# Supply.net
KiCad netlist of a schematic drawn in Altium Designer
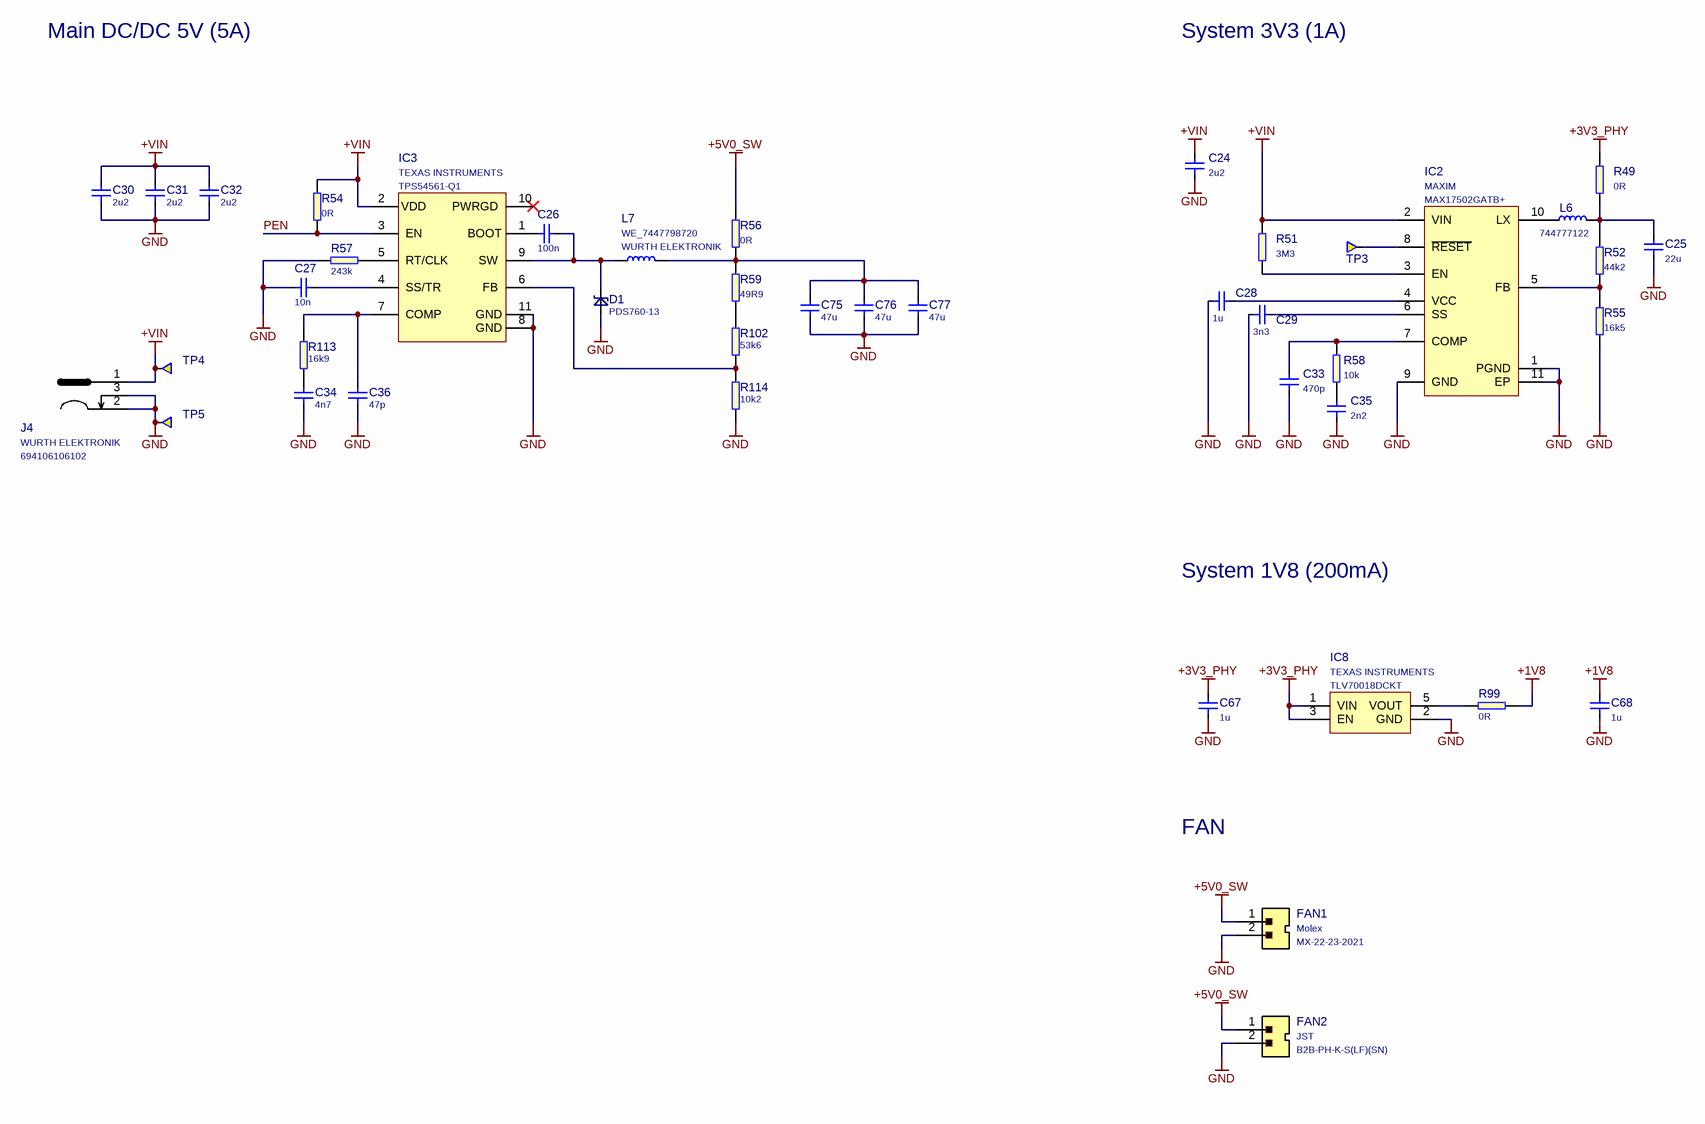
[diagram p0: Supply.SchDoc]

(export (version "E")
  (design (tool "Eeschema 10.0.6"))
  (components
    (comp (ref "C24")
      (value "2u2")
      (footprint "1210")
      (description "MLCC SMT Capacitor 2u2F 1210")
      (fields (field (name "PARTNUMBER") "C_2u2_1210"))
      (libsource (lib "altium-import") (part "root_1_C_"))
    )
    (comp (ref "C25")
      (value "22u")
      (footprint "1210")
      (description "MLCC SMT Capacitor 22uF 1210")
      (fields (field (name "PARTNUMBER") "C_22u_1210"))
      (libsource (lib "altium-import") (part "root_1_C_"))
    )
    (comp (ref "C26")
      (value "100n")
      (footprint "0603")
      (description "MLCC SMT Capacitor 100nF 0603")
      (fields (field (name "PARTNUMBER") "C_100n_0603") (field (name "MANUFACTURER") "AVX"))
      (libsource (lib "altium-import") (part "root_0_C_"))
    )
    (comp (ref "C27")
      (value "10n")
      (footprint "0402")
      (description "MLCC SMT Capacitor 10nF 0402")
      (fields (field (name "PARTNUMBER") "C_10n_0402") (field (name "MANUFACTURER") "AVX"))
      (libsource (lib "altium-import") (part "root_0_C_"))
    )
    (comp (ref "C28")
      (value "1u")
      (footprint "C_0402")
      (description "MLCC SMT Capacitor 1uF 0402")
      (fields (field (name "PARTNUMBER") "C_1u_0402"))
      (libsource (lib "altium-import") (part "root_0_C_"))
    )
    (comp (ref "C29")
      (value "3n3")
      (footprint "0603")
      (description "MLCC SMT Capacitor 3n3F 0603")
      (fields (field (name "PARTNUMBER") "C_3n3_0603"))
      (libsource (lib "altium-import") (part "root_0_C_"))
    )
    (comp (ref "C30")
      (value "2u2")
      (footprint "1206")
      (description "MLCC SMT Capacitor 2u2F 1206")
      (fields (field (name "PARTNUMBER") "C_2u2_1206") (field (name "MANUFACTURER") "Kemet"))
      (libsource (lib "altium-import") (part "root_1_C_"))
    )
    (comp (ref "C31")
      (value "2u2")
      (footprint "1206")
      (description "MLCC SMT Capacitor 2u2F 1206")
      (fields (field (name "PARTNUMBER") "C_2u2_1206") (field (name "MANUFACTURER") "Kemet"))
      (libsource (lib "altium-import") (part "root_1_C_"))
    )
    (comp (ref "C32")
      (value "2u2")
      (footprint "1206")
      (description "MLCC SMT Capacitor 2u2F 1206")
      (fields (field (name "PARTNUMBER") "C_2u2_1206") (field (name "MANUFACTURER") "Kemet"))
      (libsource (lib "altium-import") (part "root_1_C_"))
    )
    (comp (ref "C33")
      (value "470p")
      (footprint "0603")
      (description "MLCC SMT Capacitor 470pF 0603")
      (fields (field (name "PARTNUMBER") "C_470p_0603"))
      (libsource (lib "altium-import") (part "root_1_C_"))
    )
    (comp (ref "C34")
      (value "4n7")
      (footprint "0402")
      (description "MLCC SMT Capacitor 4n7F 0402")
      (fields (field (name "PARTNUMBER") "C_4n7_0402") (field (name "MANUFACTURER") "TDK"))
      (libsource (lib "altium-import") (part "root_1_C_"))
    )
    (comp (ref "C35")
      (value "2n2")
      (footprint "0603")
      (description "MLCC SMT Capacitor 2n2F 0603")
      (fields (field (name "PARTNUMBER") "C_2n2_0603"))
      (libsource (lib "altium-import") (part "root_1_C_"))
    )
    (comp (ref "C36")
      (value "47p")
      (footprint "0402")
      (description "MLCC SMT Capacitor 47pF 0402")
      (fields (field (name "PARTNUMBER") "C_47p_0402") (field (name "MANUFACTURER") "KEMET"))
      (libsource (lib "altium-import") (part "root_1_C_"))
    )
    (comp (ref "C67")
      (value "1u")
      (footprint "C_0402")
      (description "MLCC SMT Capacitor 1uF 0402")
      (fields (field (name "PARTNUMBER") "C_1u_0402"))
      (libsource (lib "altium-import") (part "root_1_C_"))
    )
    (comp (ref "C68")
      (value "1u")
      (footprint "C_0402")
      (description "MLCC SMT Capacitor 1uF 0402")
      (fields (field (name "PARTNUMBER") "C_1u_0402"))
      (libsource (lib "altium-import") (part "root_1_C_"))
    )
    (comp (ref "C75")
      (value "47u")
      (footprint "0805")
      (description "MLCC SMT Capacitor 47uF 0805")
      (fields (field (name "PARTNUMBER") "C_47u_0805") (field (name "MANUFACTURER") "KEMET"))
      (libsource (lib "altium-import") (part "root_1_C_"))
    )
    (comp (ref "C76")
      (value "47u")
      (footprint "0805")
      (description "MLCC SMT Capacitor 47uF 0805")
      (fields (field (name "PARTNUMBER") "C_47u_0805") (field (name "MANUFACTURER") "KEMET"))
      (libsource (lib "altium-import") (part "root_1_C_"))
    )
    (comp (ref "C77")
      (value "47u")
      (footprint "0805")
      (description "MLCC SMT Capacitor 47uF 0805")
      (fields (field (name "PARTNUMBER") "C_47u_0805") (field (name "MANUFACTURER") "KEMET"))
      (libsource (lib "altium-import") (part "root_1_C_"))
    )
    (comp (ref "D1")
      (value "PDS760-13")
      (footprint "PowerDI")
      (description "Schottky Diodes & Rectifiers SCHOTTKY RECTIFIER")
      (fields (field (name "MANUFACTURER") "DIODES INC."))
      (libsource (lib "altium-import") (part "root_0_Diode Schottky_"))
    )
    (comp (ref "FAN1")
      (value "MX-22-23-2021")
      (footprint "molex_2223-2021")
      (description "Pinhead connector with key")
      (fields (field (name "MANUFACTURER") "Molex") (field (name "PARTNUMBER") "022232021 A-6373-02A222"))
      (libsource (lib "altium-import") (part "root_0_molex_2223-2021_"))
    )
    (comp (ref "FAN2")
      (value "B2B-PH-K-S(LF)(SN)")
      (footprint "B2B-PH-K-S(LF)(SN)")
      (fields (field (name "MANUFACTURER") "JST"))
      (libsource (lib "coral-baseboard") (part "B2B-PH-K-S(LF)(SN)"))
    )
    (comp (ref "IC2")
      (value "MAX17502GATB+")
      (footprint "10-TDFN")
      (fields (field (name "MANUFACTURER") "MAXIM"))
      (libsource (lib "altium-import") (part "root_0_MAX17502G_"))
    )
    (comp (ref "IC3")
      (value "TPS54561-Q1")
      (footprint "WSON-10_4x4")
      (description "IC REG BCK SPLIT RAIL ADJ 10WSON")
      (fields (field (name "MANUFACTURER") "TEXAS INSTRUMENTS"))
      (libsource (lib "altium-import") (part "root_0_TPS54561_"))
    )
    (comp (ref "IC8")
      (value "TLV70018DCKT")
      (footprint "SC70-5")
      (description "Voltage Regulator, 2V to 5.5V, 175mV Dropout, 1.8Vout, 200mAout")
      (fields (field (name "MANUFACTURER") "TEXAS INSTRUMENTS"))
      (libsource (lib "altium-import") (part "root_0_TLV700_"))
    )
    (comp (ref "J4")
      (value "694106106102")
      (footprint "694106106102")
      (description "DC Power Jack Right Angled SMT Ø6.4 with 4 soldering pads & pegs WR-DC")
      (fields (field (name "MANUFACTURER") "WURTH ELEKTRONIK") (field (name "PARTNUMBER") "694106106102"))
      (libsource (lib "altium-import") (part "root_0_DC_SOCKET_2_"))
    )
    (comp (ref "L6")
      (value "744777122")
      (footprint "WE_744777122")
      (description "Surface Mount Power Inductor, WE-PD Series, 22 µH, 1.41 A, 1.7 A, Shielded, 0.11 ohm")
      (fields (field (name "MANUFACTURER") "WURTH ELEKTRONIK"))
      (libsource (lib "altium-import") (part "root_0_Inductor SMT_"))
    )
    (comp (ref "L7")
      (value "WE_7447798720")
      (footprint "WE_7447798720")
      (description "Fixed Inductors WE-PDF 1064 7.2uH 7.9A 12.8mOhm")
      (fields (field (name "PARTNUMBER") "WE_7447798720") (field (name "MANUFACTURER") "WURTH ELEKTRONIK"))
      (libsource (lib "altium-import") (part "root_0_Inductor SMT_"))
    )
    (comp (ref "R49")
      (value "0R")
      (footprint "0805")
      (description "SMT Resistor 0R 0805")
      (fields (field (name "PARTNUMBER") "R_0R_0805"))
      (libsource (lib "altium-import") (part "root_1_R_"))
    )
    (comp (ref "R51")
      (value "3M3")
      (footprint "0402")
      (description "SMT Resistor 3M3 0402")
      (fields (field (name "PARTNUMBER") "R_3M3_0402"))
      (libsource (lib "altium-import") (part "root_1_R_"))
    )
    (comp (ref "R52")
      (value "44k2")
      (footprint "0402")
      (description "SMT Resistor 0402")
      (fields (field (name "PARTNUMBER") "R_44k2_0402"))
      (libsource (lib "altium-import") (part "root_1_R_"))
    )
    (comp (ref "R54")
      (value "0R")
      (footprint "0402")
      (description "SMT Resistor 0402")
      (fields (field (name "PARTNUMBER") "R_0R_0402"))
      (libsource (lib "altium-import") (part "root_1_R_0R_0402_"))
    )
    (comp (ref "R55")
      (value "16k5")
      (footprint "0402")
      (description "RES, 16k5, 0402, 0.1%")
      (fields (field (name "PARTNUMBER") "R_16k5_0402_0.1%"))
      (libsource (lib "altium-import") (part "root_1_R_"))
    )
    (comp (ref "R56")
      (value "0R")
      (footprint "1206")
      (description "RES, 0R, 1206")
      (fields (field (name "PARTNUMBER") "R_0R_1206"))
      (libsource (lib "altium-import") (part "root_1_R_0R_1206_"))
    )
    (comp (ref "R57")
      (value "243k")
      (footprint "0402")
      (description "RES, 243k, 0402")
      (fields (field (name "PARTNUMBER") "R_243k_0402"))
      (libsource (lib "altium-import") (part "root_2_R_243k_0402_"))
    )
    (comp (ref "R58")
      (value "10k")
      (footprint "0402")
      (description "SMT Resistor 0402")
      (fields (field (name "PARTNUMBER") "R_10k_0402"))
      (libsource (lib "altium-import") (part "root_1_R_"))
    )
    (comp (ref "R59")
      (value "49R9")
      (footprint "0402")
      (description "RES, 49R9, 0402")
      (fields (field (name "PARTNUMBER") "R_49R9_0402"))
      (libsource (lib "altium-import") (part "root_1_R_49R9_0402_"))
    )
    (comp (ref "R99")
      (value "0R")
      (footprint "0603")
      (description "SMT Resistor 0R 0603")
      (fields (field (name "PARTNUMBER") "R_0R_0603"))
      (libsource (lib "altium-import") (part "root_0_R_"))
    )
    (comp (ref "R102")
      (value "53k6")
      (footprint "0402")
      (description "SMT Resistor 0402")
      (fields (field (name "PARTNUMBER") "R_53k6_0402") (field (name "MANUFACTURER") "TE CONNECTIVITY"))
      (libsource (lib "altium-import") (part "root_1_R_"))
    )
    (comp (ref "R113")
      (value "16k9")
      (footprint "0402")
      (description "SMT Resistor 0402")
      (fields (field (name "PARTNUMBER") "R_16k9_0402") (field (name "MANUFACTURER") "PANASONIC"))
      (libsource (lib "altium-import") (part "root_1_R_"))
    )
    (comp (ref "R114")
      (value "10k2")
      (footprint "0402")
      (description "RES, 10k2, 0402, 0.1%")
      (fields (field (name "PARTNUMBER") "R_10k2_0402_0.1%") (field (name "MANUFACTURER") "TE CONECTIVITY"))
      (libsource (lib "altium-import") (part "root_1_R_"))
    )
    (comp (ref "TP3")
      (value "~")
      (footprint "TP-R-2.5")
      (description "Testpad, round, 2mm")
      (fields (field (name "PARTNUMBER") "Testpad"))
      (libsource (lib "altium-import") (part "root_1_Testpad_"))
    )
    (comp (ref "TP4")
      (value "Testpad")
      (footprint "TP-R-1.5")
      (description "Testpad, round, 1.5mm")
      (libsource (lib "altium-import") (part "root_3_Testpad_"))
    )
    (comp (ref "TP5")
      (value "Testpad")
      (footprint "TP-R-1.5")
      (description "Testpad, round, 1.5mm")
      (libsource (lib "altium-import") (part "root_3_Testpad_"))
    )
  )
  (nets
    (net (code "1") (name "+1V8") (class "Default")
      (node (ref "C68") (pin "2") (pinfunction "2_2") (pintype "passive"))
      (node (ref "R99") (pin "2") (pintype "passive"))
    )
    (net (code "2") (name "+3V3_PHY") (class "Default")
      (node (ref "C67") (pin "2") (pinfunction "2_2") (pintype "passive"))
      (node (ref "IC8") (pin "1") (pinfunction "VIN_1") (pintype "passive"))
      (node (ref "IC8") (pin "3") (pinfunction "EN_3") (pintype "passive"))
      (node (ref "R49") (pin "2") (pintype "passive"))
    )
    (net (code "3") (name "+5V0_SW") (class "Default")
      (node (ref "FAN1") (pin "1") (pinfunction "1_1") (pintype "passive"))
      (node (ref "FAN2") (pin "1") (pinfunction "1_1") (pintype "passive"))
      (node (ref "R56") (pin "2") (pintype "passive"))
    )
    (net (code "4") (name "+VIN") (class "Default")
      (node (ref "C24") (pin "2") (pinfunction "2_2") (pintype "passive"))
      (node (ref "C30") (pin "2") (pinfunction "2_2") (pintype "passive"))
      (node (ref "C31") (pin "2") (pinfunction "2_2") (pintype "passive"))
      (node (ref "C32") (pin "2") (pinfunction "2_2") (pintype "passive"))
      (node (ref "IC2") (pin "2") (pinfunction "VIN_2") (pintype "passive"))
      (node (ref "IC3") (pin "2") (pinfunction "VDD_2") (pintype "passive"))
      (node (ref "J4") (pin "1") (pinfunction "1_1") (pintype "passive"))
      (node (ref "R51") (pin "2") (pintype "passive"))
      (node (ref "R54") (pin "2") (pintype "passive"))
      (node (ref "TP4") (pin "1") (pintype "passive"))
    )
    (net (code "5") (name "/PEN") (class "Default")
      (node (ref "IC3") (pin "3") (pinfunction "EN_3") (pintype "passive"))
      (node (ref "R54") (pin "1") (pintype "passive"))
    )
    (net (code "6") (name "GND") (class "Default")
      (node (ref "C24") (pin "1") (pinfunction "1_1") (pintype "passive"))
      (node (ref "C25") (pin "1") (pinfunction "1_1") (pintype "passive"))
      (node (ref "C27") (pin "1") (pinfunction "1_1") (pintype "passive"))
      (node (ref "C28") (pin "1") (pinfunction "1_1") (pintype "passive"))
      (node (ref "C29") (pin "1") (pinfunction "1_1") (pintype "passive"))
      (node (ref "C30") (pin "1") (pinfunction "1_1") (pintype "passive"))
      (node (ref "C31") (pin "1") (pinfunction "1_1") (pintype "passive"))
      (node (ref "C32") (pin "1") (pinfunction "1_1") (pintype "passive"))
      (node (ref "C33") (pin "1") (pinfunction "1_1") (pintype "passive"))
      (node (ref "C34") (pin "1") (pinfunction "1_1") (pintype "passive"))
      (node (ref "C35") (pin "1") (pinfunction "1_1") (pintype "passive"))
      (node (ref "C36") (pin "1") (pinfunction "1_1") (pintype "passive"))
      (node (ref "C67") (pin "1") (pinfunction "1_1") (pintype "passive"))
      (node (ref "C68") (pin "1") (pinfunction "1_1") (pintype "passive"))
      (node (ref "C75") (pin "1") (pinfunction "1_1") (pintype "passive"))
      (node (ref "C76") (pin "1") (pinfunction "1_1") (pintype "passive"))
      (node (ref "C77") (pin "1") (pinfunction "1_1") (pintype "passive"))
      (node (ref "D1") (pin "A") (pinfunction "A_A") (pintype "passive"))
      (node (ref "FAN1") (pin "2") (pinfunction "2_2") (pintype "passive"))
      (node (ref "FAN2") (pin "2") (pinfunction "2_2") (pintype "passive"))
      (node (ref "IC2") (pin "1") (pinfunction "PGND_1") (pintype "passive"))
      (node (ref "IC2") (pin "11") (pinfunction "EP_11") (pintype "passive"))
      (node (ref "IC2") (pin "9") (pinfunction "GND_9") (pintype "passive"))
      (node (ref "IC3") (pin "11") (pinfunction "GND_11") (pintype "passive"))
      (node (ref "IC3") (pin "8") (pinfunction "GND_8") (pintype "passive"))
      (node (ref "IC8") (pin "2") (pinfunction "GND_2") (pintype "passive"))
      (node (ref "J4") (pin "2") (pinfunction "2_2") (pintype "passive"))
      (node (ref "J4") (pin "3") (pinfunction "3_3") (pintype "passive"))
      (node (ref "R114") (pin "1") (pintype "passive"))
      (node (ref "R55") (pin "1") (pintype "passive"))
      (node (ref "R57") (pin "2") (pintype "passive"))
      (node (ref "TP5") (pin "1") (pintype "passive"))
    )
    (net (code "7") (name "Net-(C25-Pad2)") (class "Default")
      (node (ref "C25") (pin "2") (pinfunction "2_2") (pintype "passive"))
      (node (ref "L6") (pin "2") (pintype "passive"))
      (node (ref "R49") (pin "1") (pintype "passive"))
      (node (ref "R52") (pin "2") (pintype "passive"))
    )
    (net (code "8") (name "Net-(C34-Pad2)") (class "Default")
      (node (ref "C34") (pin "2") (pinfunction "2_2") (pintype "passive"))
      (node (ref "R113") (pin "1") (pintype "passive"))
    )
    (net (code "9") (name "Net-(C35-Pad2)") (class "Default")
      (node (ref "C35") (pin "2") (pinfunction "2_2") (pintype "passive"))
      (node (ref "R58") (pin "1") (pintype "passive"))
    )
    (net (code "10") (name "Net-(C75-Pad2)") (class "Default")
      (node (ref "C75") (pin "2") (pinfunction "2_2") (pintype "passive"))
      (node (ref "C76") (pin "2") (pinfunction "2_2") (pintype "passive"))
      (node (ref "C77") (pin "2") (pinfunction "2_2") (pintype "passive"))
      (node (ref "L7") (pin "2") (pintype "passive"))
      (node (ref "R56") (pin "1") (pintype "passive"))
      (node (ref "R59") (pin "2") (pintype "passive"))
    )
    (net (code "11") (name "Net-(IC2-COMP)") (class "Default")
      (node (ref "C33") (pin "2") (pinfunction "2_2") (pintype "passive"))
      (node (ref "IC2") (pin "7") (pinfunction "COMP_7") (pintype "passive"))
      (node (ref "R58") (pin "2") (pintype "passive"))
    )
    (net (code "12") (name "Net-(IC2-EN)") (class "Default")
      (node (ref "IC2") (pin "3") (pinfunction "EN_3") (pintype "passive"))
      (node (ref "R51") (pin "1") (pintype "passive"))
    )
    (net (code "13") (name "Net-(IC2-FB)") (class "Default")
      (node (ref "IC2") (pin "5") (pinfunction "FB_5") (pintype "passive"))
      (node (ref "R52") (pin "1") (pintype "passive"))
      (node (ref "R55") (pin "2") (pintype "passive"))
    )
    (net (code "14") (name "Net-(IC2-LX)") (class "Default")
      (node (ref "IC2") (pin "10") (pinfunction "LX_10") (pintype "passive"))
      (node (ref "L6") (pin "1") (pintype "passive"))
    )
    (net (code "15") (name "Net-(IC2-SS)") (class "Default")
      (node (ref "C29") (pin "2") (pinfunction "2_2") (pintype "passive"))
      (node (ref "IC2") (pin "6") (pinfunction "SS_6") (pintype "passive"))
    )
    (net (code "16") (name "Net-(IC2-VCC)") (class "Default")
      (node (ref "C28") (pin "2") (pinfunction "2_2") (pintype "passive"))
      (node (ref "IC2") (pin "4") (pinfunction "VCC_4") (pintype "passive"))
    )
    (net (code "17") (name "Net-(IC2-~{RESET})") (class "Default")
      (node (ref "IC2") (pin "8") (pinfunction "~{RESET}_8") (pintype "passive"))
      (node (ref "TP3") (pin "1") (pintype "passive"))
    )
    (net (code "18") (name "Net-(IC3-BOOT)") (class "Default")
      (node (ref "C26") (pin "1") (pinfunction "1_1") (pintype "passive"))
      (node (ref "IC3") (pin "1") (pinfunction "BOOT_1") (pintype "passive"))
    )
    (net (code "19") (name "Net-(IC3-COMP)") (class "Default")
      (node (ref "C36") (pin "2") (pinfunction "2_2") (pintype "passive"))
      (node (ref "IC3") (pin "7") (pinfunction "COMP_7") (pintype "passive"))
      (node (ref "R113") (pin "2") (pintype "passive"))
    )
    (net (code "20") (name "Net-(IC3-FB)") (class "Default")
      (node (ref "IC3") (pin "6") (pinfunction "FB_6") (pintype "passive"))
      (node (ref "R102") (pin "1") (pintype "passive"))
      (node (ref "R114") (pin "2") (pintype "passive"))
    )
    (net (code "21") (name "Net-(IC3-RT{slash}CLK)") (class "Default")
      (node (ref "IC3") (pin "5") (pinfunction "RT/CLK_5") (pintype "passive"))
      (node (ref "R57") (pin "1") (pintype "passive"))
    )
    (net (code "22") (name "Net-(IC3-SS{slash}TR)") (class "Default")
      (node (ref "C27") (pin "2") (pinfunction "2_2") (pintype "passive"))
      (node (ref "IC3") (pin "4") (pinfunction "SS/TR_4") (pintype "passive"))
    )
    (net (code "23") (name "Net-(IC3-SW)") (class "Default")
      (node (ref "C26") (pin "2") (pinfunction "2_2") (pintype "passive"))
      (node (ref "D1") (pin "C") (pinfunction "C_C") (pintype "passive"))
      (node (ref "IC3") (pin "9") (pinfunction "SW_9") (pintype "passive"))
      (node (ref "L7") (pin "1") (pintype "passive"))
    )
    (net (code "24") (name "Net-(IC8-VOUT)") (class "Default")
      (node (ref "IC8") (pin "5") (pinfunction "VOUT_5") (pintype "passive"))
      (node (ref "R99") (pin "1") (pintype "passive"))
    )
    (net (code "25") (name "Net-(R102-Pad2)") (class "Default")
      (node (ref "R102") (pin "2") (pintype "passive"))
      (node (ref "R59") (pin "1") (pintype "passive"))
    )
    (net (code "26") (name "unconnected-(IC3-PWRGD-Pad10)") (class "Default")
      (node (ref "IC3") (pin "10") (pinfunction "PWRGD_10") (pintype "passive+no_connect"))
    )
  )
)
